# BSK5.net
KiCad netlist of a schematic drawn in EAGLE
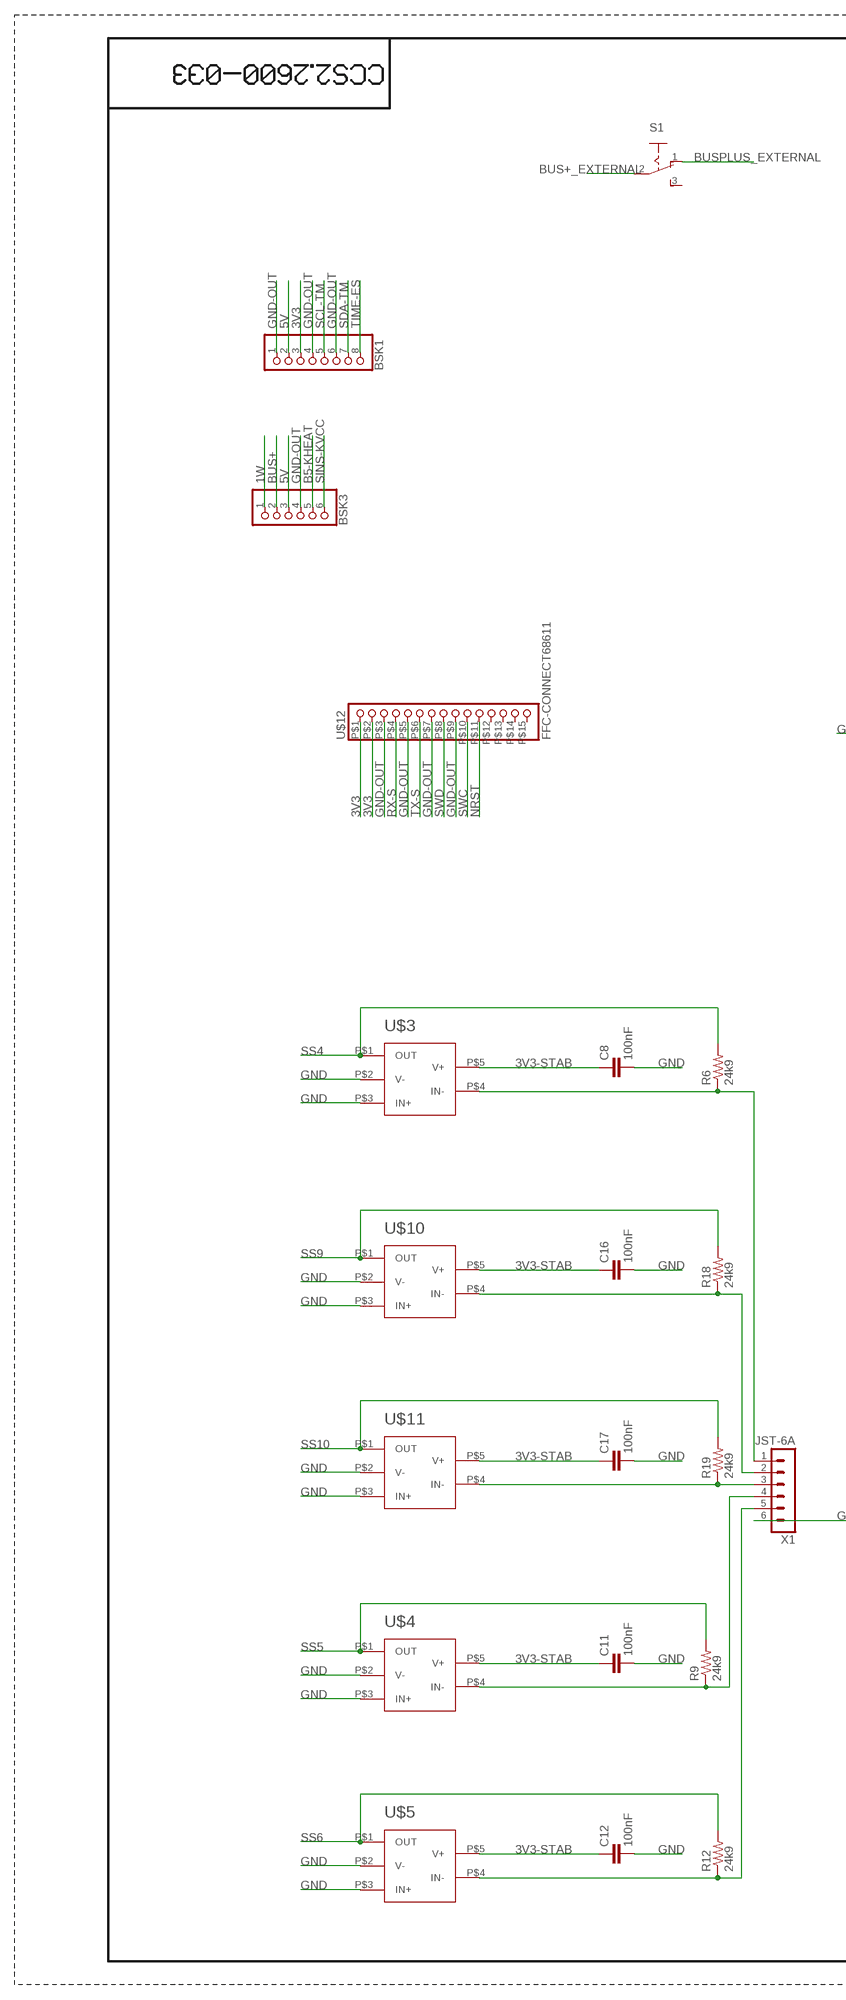
[diagram p0: schematic, sheet 1, part 1 of 3]
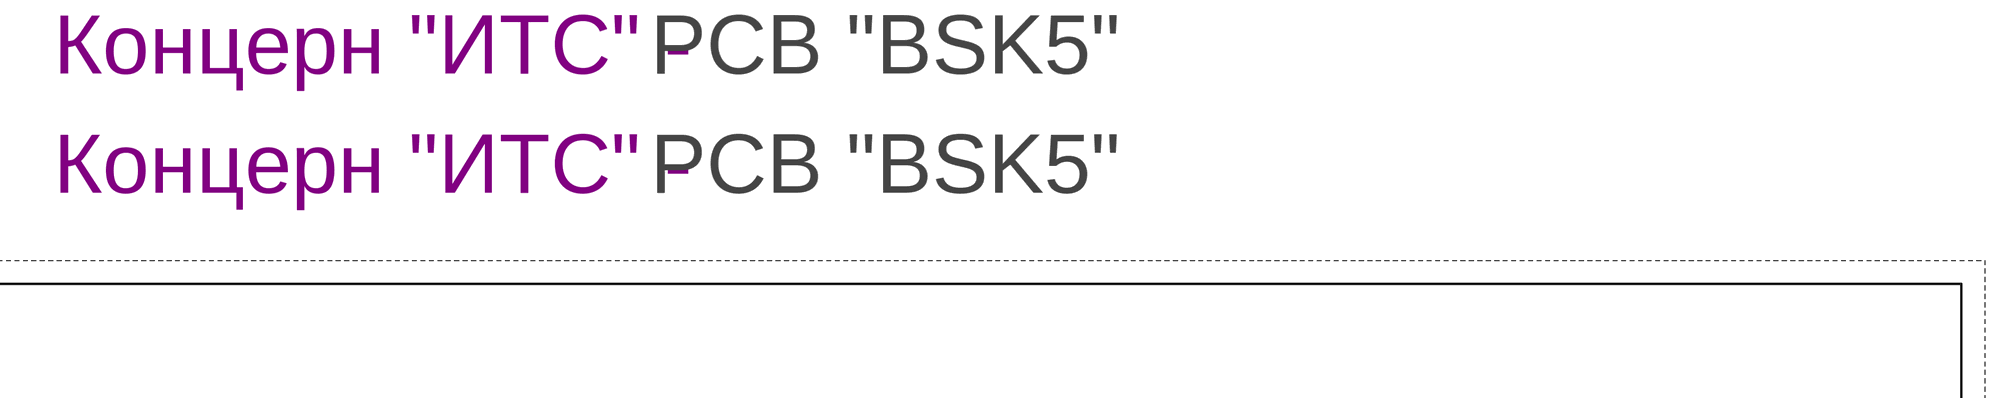
[diagram p1: schematic, sheet 1, part 2 of 3]
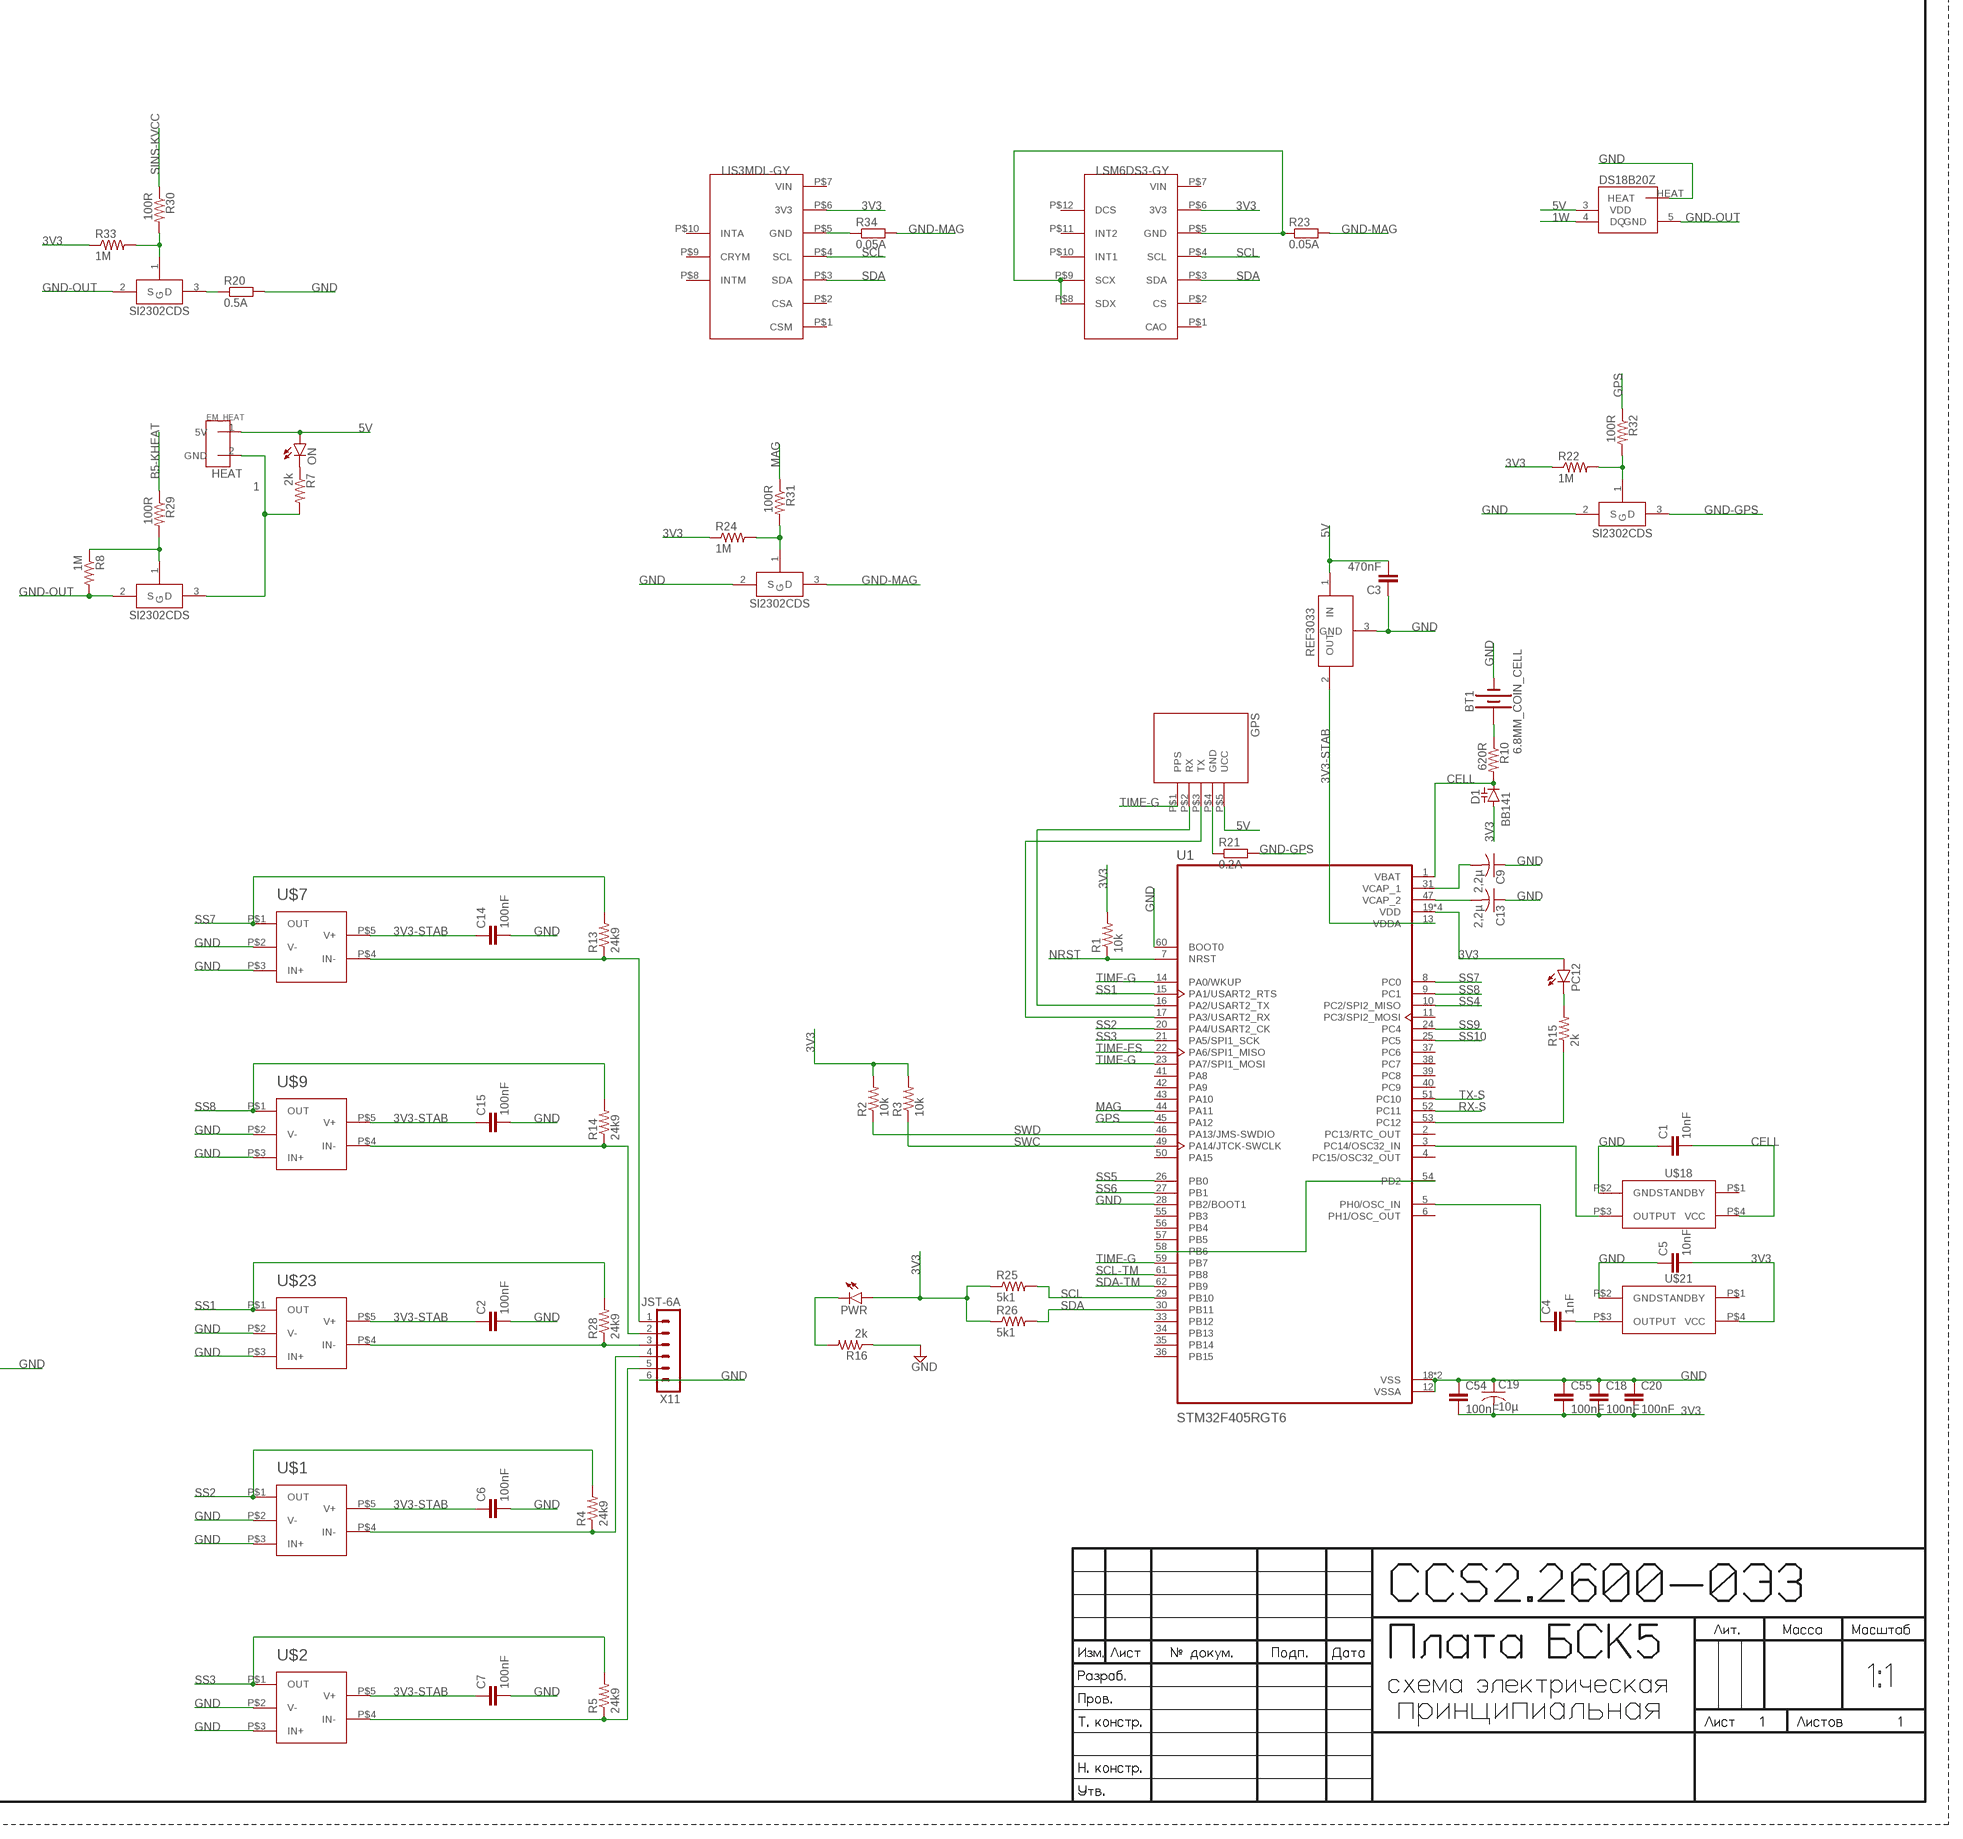
[diagram p2: schematic, sheet 1, part 3 of 3]

(export (version "E")
  (design (tool "Eeschema 10.0.6"))
  (components
    (comp (ref "BSK1")
      (value "PINHD-1X8")
      (footprint "eagle-import:1X08")
      (libsource (lib "eagle-import") (part "PINHD-1X8"))
    )
    (comp (ref "BSK3")
      (value "PINHD-1X6")
      (footprint "eagle-import:1X06")
      (libsource (lib "eagle-import") (part "PINHD-1X6"))
    )
    (comp (ref "BT1")
      (value "6.8MM_COIN_CELL")
      (footprint "eagle-import:BATTCON-6.8MM")
      (libsource (lib "eagle-import") (part "BATTERY-6.8MM_SMD"))
    )
    (comp (ref "C1")
      (value "10nF")
      (footprint "eagle-import:C0603")
      (libsource (lib "eagle-import") (part "C-EUC0603"))
    )
    (comp (ref "C2")
      (value "100nF")
      (footprint "eagle-import:C0603")
      (libsource (lib "eagle-import") (part "C-EUC0603"))
    )
    (comp (ref "C3")
      (value "470nF")
      (footprint "eagle-import:C0603")
      (libsource (lib "eagle-import") (part "C-EUC0603"))
    )
    (comp (ref "C4")
      (value "1nF")
      (footprint "eagle-import:C0603")
      (libsource (lib "eagle-import") (part "C-EUC0603"))
    )
    (comp (ref "C5")
      (value "10nF")
      (footprint "eagle-import:C0603")
      (libsource (lib "eagle-import") (part "C-EUC0603"))
    )
    (comp (ref "C6")
      (value "100nF")
      (footprint "eagle-import:C0603")
      (libsource (lib "eagle-import") (part "C-EUC0603"))
    )
    (comp (ref "C7")
      (value "100nF")
      (footprint "eagle-import:C0603")
      (libsource (lib "eagle-import") (part "C-EUC0603"))
    )
    (comp (ref "C8")
      (value "100nF")
      (footprint "eagle-import:C0603")
      (libsource (lib "eagle-import") (part "C-EUC0603"))
    )
    (comp (ref "C9")
      (value "2,2µ")
      (footprint "eagle-import:C0603")
      (libsource (lib "eagle-import") (part "C-USC0603"))
    )
    (comp (ref "C11")
      (value "100nF")
      (footprint "eagle-import:C0603")
      (libsource (lib "eagle-import") (part "C-EUC0603"))
    )
    (comp (ref "C12")
      (value "100nF")
      (footprint "eagle-import:C0603")
      (libsource (lib "eagle-import") (part "C-EUC0603"))
    )
    (comp (ref "C13")
      (value "2,2µ")
      (footprint "eagle-import:C0603")
      (libsource (lib "eagle-import") (part "C-USC0603"))
    )
    (comp (ref "C14")
      (value "100nF")
      (footprint "eagle-import:C0603")
      (libsource (lib "eagle-import") (part "C-EUC0603"))
    )
    (comp (ref "C15")
      (value "100nF")
      (footprint "eagle-import:C0603")
      (libsource (lib "eagle-import") (part "C-EUC0603"))
    )
    (comp (ref "C16")
      (value "100nF")
      (footprint "eagle-import:C0603")
      (libsource (lib "eagle-import") (part "C-EUC0603"))
    )
    (comp (ref "C17")
      (value "100nF")
      (footprint "eagle-import:C0603")
      (libsource (lib "eagle-import") (part "C-EUC0603"))
    )
    (comp (ref "C18")
      (value "100nF")
      (footprint "eagle-import:C0603")
      (libsource (lib "eagle-import") (part "C-EUC0603"))
    )
    (comp (ref "C19")
      (value "10µ")
      (footprint "eagle-import:C1206")
      (libsource (lib "eagle-import") (part "C-USC1206"))
    )
    (comp (ref "C20")
      (value "100nF")
      (footprint "eagle-import:C0603")
      (libsource (lib "eagle-import") (part "C-EUC0603"))
    )
    (comp (ref "C54")
      (value "100nF")
      (footprint "eagle-import:C0603")
      (libsource (lib "eagle-import") (part "C-EUC0603"))
    )
    (comp (ref "C55")
      (value "100nF")
      (footprint "eagle-import:C0603")
      (libsource (lib "eagle-import") (part "C-EUC0603"))
    )
    (comp (ref "D1")
      (value "BB141")
      (footprint "eagle-import:SOD523")
      (libsource (lib "eagle-import") (part "BB141"))
    )
    (comp (ref "DS18B20Z1")
      (value "DS18B20Z")
      (footprint "eagle-import:SOIC8+HEAT_S")
      (libsource (lib "eagle-import") (part "DS18B20Z"))
    )
    (comp (ref "GPS")
      (value "GPSNEO6M")
      (footprint "eagle-import:GPS-NEO6M")
      (libsource (lib "eagle-import") (part "GPSNEO6M"))
    )
    (comp (ref "HEATER")
      (value "EM_HEAT")
      (footprint "eagle-import:EM_HEAT")
      (libsource (lib "eagle-import") (part "EM_HEAT"))
    )
    (comp (ref "LIS3MDL-GY")
      (value "LIS3MDL-GY")
      (footprint "eagle-import:LIS3MDL-GY")
      (libsource (lib "eagle-import") (part "LIS3MDL-GY"))
    )
    (comp (ref "LSM6DS3-GY")
      (value "LSM6DS3-GY")
      (footprint "eagle-import:LSM6DS3-GY")
      (libsource (lib "eagle-import") (part "LSM6DS3-GY"))
    )
    (comp (ref "ON")
      (value "LEDCHIPLED_0603")
      (footprint "eagle-import:CHIPLED_0603")
      (libsource (lib "eagle-import") (part "LEDCHIPLED_0603"))
    )
    (comp (ref "PC12")
      (value "LEDCHIPLED_0603")
      (footprint "eagle-import:CHIPLED_0603")
      (libsource (lib "eagle-import") (part "LEDCHIPLED_0603"))
    )
    (comp (ref "PWR")
      (value "LEDCHIPLED_0603")
      (footprint "eagle-import:CHIPLED_0603")
      (libsource (lib "eagle-import") (part "LEDCHIPLED_0603"))
    )
    (comp (ref "R1")
      (value "10k")
      (footprint "eagle-import:R0603")
      (libsource (lib "eagle-import") (part "R-US_R0603"))
    )
    (comp (ref "R2")
      (value "10k")
      (footprint "eagle-import:R0603")
      (libsource (lib "eagle-import") (part "R-US_R0603"))
    )
    (comp (ref "R3")
      (value "10k")
      (footprint "eagle-import:R0603")
      (libsource (lib "eagle-import") (part "R-US_R0603"))
    )
    (comp (ref "R4")
      (value "24k9")
      (footprint "eagle-import:R0603")
      (libsource (lib "eagle-import") (part "R-US_R0603"))
    )
    (comp (ref "R5")
      (value "24k9")
      (footprint "eagle-import:R0603")
      (libsource (lib "eagle-import") (part "R-US_R0603"))
    )
    (comp (ref "R6")
      (value "24k9")
      (footprint "eagle-import:R0603")
      (libsource (lib "eagle-import") (part "R-US_R0603"))
    )
    (comp (ref "R7")
      (value "2k")
      (footprint "eagle-import:R0603")
      (libsource (lib "eagle-import") (part "R-US_R0603"))
    )
    (comp (ref "R8")
      (value "1M")
      (footprint "eagle-import:R0603")
      (libsource (lib "eagle-import") (part "R-US_R0603"))
    )
    (comp (ref "R9")
      (value "24k9")
      (footprint "eagle-import:R0603")
      (libsource (lib "eagle-import") (part "R-US_R0603"))
    )
    (comp (ref "R10")
      (value "620R")
      (footprint "eagle-import:R0603")
      (libsource (lib "eagle-import") (part "R-US_R0603"))
    )
    (comp (ref "R12")
      (value "24k9")
      (footprint "eagle-import:R0603")
      (libsource (lib "eagle-import") (part "R-US_R0603"))
    )
    (comp (ref "R13")
      (value "24k9")
      (footprint "eagle-import:R0603")
      (libsource (lib "eagle-import") (part "R-US_R0603"))
    )
    (comp (ref "R14")
      (value "24k9")
      (footprint "eagle-import:R0603")
      (libsource (lib "eagle-import") (part "R-US_R0603"))
    )
    (comp (ref "R15")
      (value "2k")
      (footprint "eagle-import:R0603")
      (libsource (lib "eagle-import") (part "R-US_R0603"))
    )
    (comp (ref "R16")
      (value "2k")
      (footprint "eagle-import:R0603")
      (libsource (lib "eagle-import") (part "R-US_R0603"))
    )
    (comp (ref "R18")
      (value "24k9")
      (footprint "eagle-import:R0603")
      (libsource (lib "eagle-import") (part "R-US_R0603"))
    )
    (comp (ref "R19")
      (value "24k9")
      (footprint "eagle-import:R0603")
      (libsource (lib "eagle-import") (part "R-US_R0603"))
    )
    (comp (ref "R20")
      (value "0.5A")
      (footprint "eagle-import:R1210")
      (libsource (lib "eagle-import") (part "R-EU_R1210"))
    )
    (comp (ref "R21")
      (value "0.2A")
      (footprint "eagle-import:R1210")
      (libsource (lib "eagle-import") (part "R-EU_R1210"))
    )
    (comp (ref "R22")
      (value "1M")
      (footprint "eagle-import:R0603")
      (libsource (lib "eagle-import") (part "R-US_R0603"))
    )
    (comp (ref "R23")
      (value "0.05A")
      (footprint "eagle-import:R1210")
      (libsource (lib "eagle-import") (part "R-EU_R1210"))
    )
    (comp (ref "R24")
      (value "1M")
      (footprint "eagle-import:R0603")
      (libsource (lib "eagle-import") (part "R-US_R0603"))
    )
    (comp (ref "R25")
      (value "5k1")
      (footprint "eagle-import:R0603")
      (libsource (lib "eagle-import") (part "R-US_R0603"))
    )
    (comp (ref "R26")
      (value "5k1")
      (footprint "eagle-import:R0603")
      (libsource (lib "eagle-import") (part "R-US_R0603"))
    )
    (comp (ref "R28")
      (value "24k9")
      (footprint "eagle-import:R0603")
      (libsource (lib "eagle-import") (part "R-US_R0603"))
    )
    (comp (ref "R29")
      (value "100R")
      (footprint "eagle-import:R0603")
      (libsource (lib "eagle-import") (part "R-US_R0603"))
    )
    (comp (ref "R30")
      (value "100R")
      (footprint "eagle-import:R0603")
      (libsource (lib "eagle-import") (part "R-US_R0603"))
    )
    (comp (ref "R31")
      (value "100R")
      (footprint "eagle-import:R0603")
      (libsource (lib "eagle-import") (part "R-US_R0603"))
    )
    (comp (ref "R32")
      (value "100R")
      (footprint "eagle-import:R0603")
      (libsource (lib "eagle-import") (part "R-US_R0603"))
    )
    (comp (ref "R33")
      (value "1M")
      (footprint "eagle-import:R0603")
      (libsource (lib "eagle-import") (part "R-US_R0603"))
    )
    (comp (ref "R34")
      (value "0.05A")
      (footprint "eagle-import:R1210")
      (libsource (lib "eagle-import") (part "R-EU_R1210"))
    )
    (comp (ref "S1")
      (value "UNICS-SWITCH")
      (footprint "eagle-import:UNICS-SWITCH")
      (libsource (lib "eagle-import") (part "UNICS-SWITCH"))
    )
    (comp (ref "U$1")
      (value "LMC7101")
      (footprint "eagle-import:LMC7101")
      (libsource (lib "eagle-import") (part "LMC7101"))
    )
    (comp (ref "U$2")
      (value "LMC7101")
      (footprint "eagle-import:LMC7101")
      (libsource (lib "eagle-import") (part "LMC7101"))
    )
    (comp (ref "U$3")
      (value "LMC7101")
      (footprint "eagle-import:LMC7101")
      (libsource (lib "eagle-import") (part "LMC7101"))
    )
    (comp (ref "U$4")
      (value "LMC7101")
      (footprint "eagle-import:LMC7101")
      (libsource (lib "eagle-import") (part "LMC7101"))
    )
    (comp (ref "U$5")
      (value "LMC7101")
      (footprint "eagle-import:LMC7101")
      (libsource (lib "eagle-import") (part "LMC7101"))
    )
    (comp (ref "U$6")
      (value "REF3033")
      (footprint "eagle-import:SOT23-3")
      (libsource (lib "eagle-import") (part "REF3033"))
    )
    (comp (ref "U$7")
      (value "LMC7101")
      (footprint "eagle-import:LMC7101")
      (libsource (lib "eagle-import") (part "LMC7101"))
    )
    (comp (ref "U$8")
      (value "SI2302CDS")
      (footprint "eagle-import:SOT23-3")
      (libsource (lib "eagle-import") (part "SI2302CDS"))
    )
    (comp (ref "U$9")
      (value "LMC7101")
      (footprint "eagle-import:LMC7101")
      (libsource (lib "eagle-import") (part "LMC7101"))
    )
    (comp (ref "U$10")
      (value "LMC7101")
      (footprint "eagle-import:LMC7101")
      (libsource (lib "eagle-import") (part "LMC7101"))
    )
    (comp (ref "U$11")
      (value "LMC7101")
      (footprint "eagle-import:LMC7101")
      (libsource (lib "eagle-import") (part "LMC7101"))
    )
    (comp (ref "U$12")
      (value "FFC-CONNECT68611")
      (footprint "eagle-import:68611")
      (libsource (lib "eagle-import") (part "FFC-CONNECT68611"))
    )
    (comp (ref "U$13")
      (value "PCB \"BSK5\"")
      (footprint "eagle-import:ITS-LOGO")
      (libsource (lib "eagle-import") (part "ITS-LOGOPCB-{dblquote}{dblquote}"))
    )
    (comp (ref "U$18")
      (value "Q32.768")
      (footprint "eagle-import:Q32.768")
      (libsource (lib "eagle-import") (part "Q32.768"))
    )
    (comp (ref "U$19")
      (value "SI2302CDS")
      (footprint "eagle-import:SOT23-3")
      (libsource (lib "eagle-import") (part "SI2302CDS"))
    )
    (comp (ref "U$20")
      (value "SI2302CDS")
      (footprint "eagle-import:SOT23-3")
      (libsource (lib "eagle-import") (part "SI2302CDS"))
    )
    (comp (ref "U$21")
      (value "Q24")
      (footprint "eagle-import:Q24")
      (libsource (lib "eagle-import") (part "Q24"))
    )
    (comp (ref "U$22")
      (value "SI2302CDS")
      (footprint "eagle-import:SOT23-3")
      (libsource (lib "eagle-import") (part "SI2302CDS"))
    )
    (comp (ref "U$23")
      (value "LMC7101")
      (footprint "eagle-import:LMC7101")
      (libsource (lib "eagle-import") (part "LMC7101"))
    )
    (comp (ref "U$26")
      (value "PCB \"BSK5\"")
      (footprint "eagle-import:ITS-LOGO")
      (libsource (lib "eagle-import") (part "ITS-LOGOPCB-{dblquote}{dblquote}"))
    )
    (comp (ref "U1")
      (value "STM32F405RGT6")
      (footprint "eagle-import:QFP50P1200X1200X160-64N")
      (fields (field (name "DIGI-KEY_PART_NUMBER") "497-11767-ND") (field (name "MF") "STMicroelectronics"))
      (libsource (lib "eagle-import") (part "STM32F405RGT6"))
    )
    (comp (ref "X1")
      (value "JST-6A")
      (footprint "eagle-import:B6B-EH-A")
      (libsource (lib "eagle-import") (part "JST-6A"))
    )
    (comp (ref "X11")
      (value "JST-6A")
      (footprint "eagle-import:B6B-EH-A")
      (libsource (lib "eagle-import") (part "JST-6A"))
    )
  )
  (nets
    (net (code "1") (name "/1") (class "Default")
      (node (ref "HEATER") (pin "2") (pinfunction "GND_2") (pintype "bidirectional"))
      (node (ref "R7") (pin "2") (pinfunction "2_2") (pintype "passive"))
      (node (ref "U$8") (pin "3") (pinfunction "D_3") (pintype "bidirectional"))
    )
    (net (code "2") (name "/1W") (class "Default")
      (node (ref "BSK3") (pin "1") (pinfunction "1_1") (pintype "passive"))
      (node (ref "DS18B20Z1") (pin "4") (pinfunction "DQ_4") (pintype "bidirectional"))
    )
    (net (code "3") (name "/3V3") (class "Default")
      (node (ref "BSK1") (pin "3") (pinfunction "3_3") (pintype "passive"))
      (node (ref "C18") (pin "2") (pinfunction "2_2") (pintype "passive"))
      (node (ref "C19") (pin "2") (pinfunction "2_2") (pintype "passive"))
      (node (ref "C20") (pin "2") (pinfunction "2_2") (pintype "passive"))
      (node (ref "C5") (pin "2") (pinfunction "2_2") (pintype "passive"))
      (node (ref "C54") (pin "2") (pinfunction "2_2") (pintype "passive"))
      (node (ref "C55") (pin "2") (pinfunction "2_2") (pintype "passive"))
      (node (ref "D1") (pin "A") (pinfunction "A_A") (pintype "passive"))
      (node (ref "LIS3MDL-GY") (pin "P$6") (pinfunction "3V3_P$6") (pintype "bidirectional"))
      (node (ref "LSM6DS3-GY") (pin "P$6") (pinfunction "3V3_P$6") (pintype "bidirectional"))
      (node (ref "PC12") (pin "A") (pinfunction "A_A") (pintype "passive"))
      (node (ref "PWR") (pin "A") (pinfunction "A_A") (pintype "passive"))
      (node (ref "R1") (pin "2") (pinfunction "2_2") (pintype "passive"))
      (node (ref "R2") (pin "2") (pinfunction "2_2") (pintype "passive"))
      (node (ref "R22") (pin "1") (pinfunction "1_1") (pintype "passive"))
      (node (ref "R24") (pin "1") (pinfunction "1_1") (pintype "passive"))
      (node (ref "R25") (pin "1") (pinfunction "1_1") (pintype "passive"))
      (node (ref "R26") (pin "1") (pinfunction "1_1") (pintype "passive"))
      (node (ref "R3") (pin "2") (pinfunction "2_2") (pintype "passive"))
      (node (ref "R33") (pin "1") (pinfunction "1_1") (pintype "passive"))
      (node (ref "U$12") (pin "P$1") (pinfunction "1_P$1") (pintype "passive"))
      (node (ref "U$12") (pin "P$2") (pinfunction "2_P$2") (pintype "passive"))
      (node (ref "U$21") (pin "P$4") (pinfunction "VCC_P$4") (pintype "bidirectional"))
      (node (ref "U1") (pin "19") (pinfunction "VDD_19") (pintype "power_in"))
      (node (ref "U1") (pin "32") (pinfunction "VDD_32") (pintype "power_in"))
      (node (ref "U1") (pin "48") (pinfunction "VDD_48") (pintype "power_in"))
      (node (ref "U1") (pin "64") (pinfunction "VDD_64") (pintype "power_in"))
    )
    (net (code "4") (name "/3V3-STAB") (class "Default")
      (node (ref "C11") (pin "1") (pinfunction "1_1") (pintype "passive"))
      (node (ref "C12") (pin "1") (pinfunction "1_1") (pintype "passive"))
      (node (ref "C14") (pin "1") (pinfunction "1_1") (pintype "passive"))
      (node (ref "C15") (pin "1") (pinfunction "1_1") (pintype "passive"))
      (node (ref "C16") (pin "1") (pinfunction "1_1") (pintype "passive"))
      (node (ref "C17") (pin "1") (pinfunction "1_1") (pintype "passive"))
      (node (ref "C2") (pin "1") (pinfunction "1_1") (pintype "passive"))
      (node (ref "C6") (pin "1") (pinfunction "1_1") (pintype "passive"))
      (node (ref "C7") (pin "1") (pinfunction "1_1") (pintype "passive"))
      (node (ref "C8") (pin "1") (pinfunction "1_1") (pintype "passive"))
      (node (ref "U$1") (pin "P$5") (pinfunction "V+_P$5") (pintype "bidirectional"))
      (node (ref "U$10") (pin "P$5") (pinfunction "V+_P$5") (pintype "bidirectional"))
      (node (ref "U$11") (pin "P$5") (pinfunction "V+_P$5") (pintype "bidirectional"))
      (node (ref "U$2") (pin "P$5") (pinfunction "V+_P$5") (pintype "bidirectional"))
      (node (ref "U$23") (pin "P$5") (pinfunction "V+_P$5") (pintype "bidirectional"))
      (node (ref "U$3") (pin "P$5") (pinfunction "V+_P$5") (pintype "bidirectional"))
      (node (ref "U$4") (pin "P$5") (pinfunction "V+_P$5") (pintype "bidirectional"))
      (node (ref "U$5") (pin "P$5") (pinfunction "V+_P$5") (pintype "bidirectional"))
      (node (ref "U$6") (pin "2") (pinfunction "OUT_2") (pintype "output"))
      (node (ref "U$7") (pin "P$5") (pinfunction "V+_P$5") (pintype "bidirectional"))
      (node (ref "U$9") (pin "P$5") (pinfunction "V+_P$5") (pintype "bidirectional"))
      (node (ref "U1") (pin "13") (pinfunction "VDDA_13") (pintype "power_in"))
    )
    (net (code "5") (name "/5V") (class "Default")
      (node (ref "BSK1") (pin "2") (pinfunction "2_2") (pintype "passive"))
      (node (ref "BSK3") (pin "3") (pinfunction "3_3") (pintype "passive"))
      (node (ref "C3") (pin "2") (pinfunction "2_2") (pintype "passive"))
      (node (ref "DS18B20Z1") (pin "3") (pinfunction "VDD_3") (pintype "bidirectional"))
      (node (ref "GPS") (pin "P$5") (pinfunction "UCC_P$5") (pintype "bidirectional"))
      (node (ref "HEATER") (pin "1") (pinfunction "5V_1") (pintype "bidirectional"))
      (node (ref "ON") (pin "A") (pinfunction "A_A") (pintype "passive"))
      (node (ref "U$6") (pin "1") (pinfunction "IN_1") (pintype "input"))
    )
    (net (code "6") (name "/B5-KHEAT") (class "Default")
      (node (ref "BSK3") (pin "5") (pinfunction "5_5") (pintype "passive"))
      (node (ref "R29") (pin "1") (pinfunction "1_1") (pintype "passive"))
    )
    (net (code "7") (name "/BUS+") (class "Default")
      (node (ref "BSK3") (pin "2") (pinfunction "2_2") (pintype "passive"))
    )
    (net (code "8") (name "/BUS+_EXTERNAL") (class "Default")
      (node (ref "S1") (pin "2") (pinfunction "P_2") (pintype "passive"))
    )
    (net (code "9") (name "/BUSPLUS_EXTERNAL") (class "Default")
      (node (ref "S1") (pin "1") (pinfunction "O_1") (pintype "passive"))
    )
    (net (code "10") (name "/CELL") (class "Default")
      (node (ref "C1") (pin "2") (pinfunction "2_2") (pintype "passive"))
      (node (ref "D1") (pin "C") (pinfunction "C_C") (pintype "passive"))
      (node (ref "R10") (pin "2") (pinfunction "2_2") (pintype "passive"))
      (node (ref "U$18") (pin "P$4") (pinfunction "VCC_P$4") (pintype "bidirectional"))
      (node (ref "U1") (pin "1") (pinfunction "VBAT_1") (pintype "power_in"))
    )
    (net (code "11") (name "/GND-GPS") (class "Default")
      (node (ref "R21") (pin "2") (pinfunction "2_2") (pintype "passive"))
      (node (ref "U$20") (pin "3") (pinfunction "D_3") (pintype "bidirectional"))
    )
    (net (code "12") (name "/GND-MAG") (class "Default")
      (node (ref "R23") (pin "2") (pinfunction "2_2") (pintype "passive"))
      (node (ref "R34") (pin "2") (pinfunction "2_2") (pintype "passive"))
      (node (ref "U$19") (pin "3") (pinfunction "D_3") (pintype "bidirectional"))
    )
    (net (code "13") (name "/GND-OUT") (class "Default")
      (node (ref "BSK1") (pin "1") (pinfunction "1_1") (pintype "passive"))
      (node (ref "BSK1") (pin "4") (pinfunction "4_4") (pintype "passive"))
      (node (ref "BSK1") (pin "6") (pinfunction "6_6") (pintype "passive"))
      (node (ref "BSK3") (pin "4") (pinfunction "4_4") (pintype "passive"))
      (node (ref "DS18B20Z1") (pin "5") (pinfunction "GND_5") (pintype "bidirectional"))
      (node (ref "R8") (pin "2") (pinfunction "2_2") (pintype "passive"))
      (node (ref "U$12") (pin "P$3") (pinfunction "3_P$3") (pintype "passive"))
      (node (ref "U$12") (pin "P$5") (pinfunction "5_P$5") (pintype "passive"))
      (node (ref "U$12") (pin "P$7") (pinfunction "7_P$7") (pintype "passive"))
      (node (ref "U$12") (pin "P$9") (pinfunction "9_P$9") (pintype "passive"))
      (node (ref "U$22") (pin "2") (pinfunction "S_2") (pintype "bidirectional"))
      (node (ref "U$8") (pin "2") (pinfunction "S_2") (pintype "bidirectional"))
    )
    (net (code "14") (name "/GPS") (class "Default")
      (node (ref "R32") (pin "1") (pinfunction "1_1") (pintype "passive"))
      (node (ref "U1") (pin "45") (pinfunction "PA12_45") (pintype "bidirectional"))
    )
    (net (code "15") (name "/MAG") (class "Default")
      (node (ref "R31") (pin "1") (pinfunction "1_1") (pintype "passive"))
      (node (ref "U1") (pin "44") (pinfunction "PA11_44") (pintype "bidirectional"))
    )
    (net (code "16") (name "/NRST") (class "Default")
      (node (ref "R1") (pin "1") (pinfunction "1_1") (pintype "passive"))
      (node (ref "U$12") (pin "P$11") (pinfunction "11_P$11") (pintype "passive"))
      (node (ref "U1") (pin "7") (pinfunction "NRST_7") (pintype "bidirectional"))
    )
    (net (code "17") (name "/RX-S") (class "Default")
      (node (ref "U$12") (pin "P$4") (pinfunction "4_P$4") (pintype "passive"))
      (node (ref "U1") (pin "52") (pinfunction "PC11_52") (pintype "bidirectional"))
    )
    (net (code "18") (name "/SCL") (class "Default")
      (node (ref "LIS3MDL-GY") (pin "P$4") (pinfunction "SCL_P$4") (pintype "bidirectional"))
      (node (ref "LSM6DS3-GY") (pin "P$4") (pinfunction "SCL_P$4") (pintype "bidirectional"))
      (node (ref "R25") (pin "2") (pinfunction "2_2") (pintype "passive"))
      (node (ref "U1") (pin "29") (pinfunction "PB10_29") (pintype "bidirectional"))
    )
    (net (code "19") (name "/SCL-TM") (class "Default")
      (node (ref "BSK1") (pin "5") (pinfunction "5_5") (pintype "passive"))
      (node (ref "U1") (pin "61") (pinfunction "PB8_61") (pintype "bidirectional"))
    )
    (net (code "20") (name "/SDA") (class "Default")
      (node (ref "LIS3MDL-GY") (pin "P$3") (pinfunction "SDA_P$3") (pintype "bidirectional"))
      (node (ref "LSM6DS3-GY") (pin "P$3") (pinfunction "SDA_P$3") (pintype "bidirectional"))
      (node (ref "R26") (pin "2") (pinfunction "2_2") (pintype "passive"))
      (node (ref "U1") (pin "30") (pinfunction "PB11_30") (pintype "bidirectional"))
    )
    (net (code "21") (name "/SDA-TM") (class "Default")
      (node (ref "BSK1") (pin "7") (pinfunction "7_7") (pintype "passive"))
      (node (ref "U1") (pin "62") (pinfunction "PB9_62") (pintype "bidirectional"))
    )
    (net (code "22") (name "/SINS-KVCC") (class "Default")
      (node (ref "BSK3") (pin "6") (pinfunction "6_6") (pintype "passive"))
      (node (ref "R30") (pin "1") (pinfunction "1_1") (pintype "passive"))
    )
    (net (code "23") (name "/SS1") (class "Default")
      (node (ref "R28") (pin "2") (pinfunction "2_2") (pintype "passive"))
      (node (ref "U$23") (pin "P$1") (pinfunction "OUT_P$1") (pintype "bidirectional"))
      (node (ref "U1") (pin "15") (pinfunction "PA1/USART2_RTS_15") (pintype "bidirectional"))
    )
    (net (code "24") (name "/SS2") (class "Default")
      (node (ref "R4") (pin "2") (pinfunction "2_2") (pintype "passive"))
      (node (ref "U$1") (pin "P$1") (pinfunction "OUT_P$1") (pintype "bidirectional"))
      (node (ref "U1") (pin "20") (pinfunction "PA4/USART2_CK_20") (pintype "bidirectional"))
    )
    (net (code "25") (name "/SS3") (class "Default")
      (node (ref "R5") (pin "2") (pinfunction "2_2") (pintype "passive"))
      (node (ref "U$2") (pin "P$1") (pinfunction "OUT_P$1") (pintype "bidirectional"))
      (node (ref "U1") (pin "21") (pinfunction "PA5/SPI1_SCK_21") (pintype "bidirectional"))
    )
    (net (code "26") (name "/SS4") (class "Default")
      (node (ref "R6") (pin "2") (pinfunction "2_2") (pintype "passive"))
      (node (ref "U$3") (pin "P$1") (pinfunction "OUT_P$1") (pintype "bidirectional"))
      (node (ref "U1") (pin "10") (pinfunction "PC2/SPI2_MISO_10") (pintype "bidirectional"))
    )
    (net (code "27") (name "/SS5") (class "Default")
      (node (ref "R9") (pin "2") (pinfunction "2_2") (pintype "passive"))
      (node (ref "U$4") (pin "P$1") (pinfunction "OUT_P$1") (pintype "bidirectional"))
      (node (ref "U1") (pin "26") (pinfunction "PB0_26") (pintype "bidirectional"))
    )
    (net (code "28") (name "/SS6") (class "Default")
      (node (ref "R12") (pin "2") (pinfunction "2_2") (pintype "passive"))
      (node (ref "U$5") (pin "P$1") (pinfunction "OUT_P$1") (pintype "bidirectional"))
      (node (ref "U1") (pin "27") (pinfunction "PB1_27") (pintype "bidirectional"))
    )
    (net (code "29") (name "/SS7") (class "Default")
      (node (ref "R13") (pin "2") (pinfunction "2_2") (pintype "passive"))
      (node (ref "U$7") (pin "P$1") (pinfunction "OUT_P$1") (pintype "bidirectional"))
      (node (ref "U1") (pin "8") (pinfunction "PC0_8") (pintype "bidirectional"))
    )
    (net (code "30") (name "/SS8") (class "Default")
      (node (ref "R14") (pin "2") (pinfunction "2_2") (pintype "passive"))
      (node (ref "U$9") (pin "P$1") (pinfunction "OUT_P$1") (pintype "bidirectional"))
      (node (ref "U1") (pin "9") (pinfunction "PC1_9") (pintype "bidirectional"))
    )
    (net (code "31") (name "/SS9") (class "Default")
      (node (ref "R18") (pin "2") (pinfunction "2_2") (pintype "passive"))
      (node (ref "U$10") (pin "P$1") (pinfunction "OUT_P$1") (pintype "bidirectional"))
      (node (ref "U1") (pin "24") (pinfunction "PC4_24") (pintype "bidirectional"))
    )
    (net (code "32") (name "/SS10") (class "Default")
      (node (ref "R19") (pin "2") (pinfunction "2_2") (pintype "passive"))
      (node (ref "U$11") (pin "P$1") (pinfunction "OUT_P$1") (pintype "bidirectional"))
      (node (ref "U1") (pin "25") (pinfunction "PC5_25") (pintype "bidirectional"))
    )
    (net (code "33") (name "/SWC") (class "Default")
      (node (ref "R3") (pin "1") (pinfunction "1_1") (pintype "passive"))
      (node (ref "U$12") (pin "P$10") (pinfunction "10_P$10") (pintype "passive"))
      (node (ref "U1") (pin "49") (pinfunction "PA14/JTCK-SWCLK_49") (pintype "bidirectional"))
    )
    (net (code "34") (name "/SWD") (class "Default")
      (node (ref "R2") (pin "1") (pinfunction "1_1") (pintype "passive"))
      (node (ref "U$12") (pin "P$8") (pinfunction "8_P$8") (pintype "passive"))
      (node (ref "U1") (pin "46") (pinfunction "PA13/JMS-SWDIO_46") (pintype "bidirectional"))
    )
    (net (code "35") (name "/TIME-ES") (class "Default")
      (node (ref "BSK1") (pin "8") (pinfunction "8_8") (pintype "passive"))
      (node (ref "U1") (pin "22") (pinfunction "PA6/SPI1_MISO_22") (pintype "bidirectional"))
    )
    (net (code "36") (name "/TIME-G") (class "Default")
      (node (ref "GPS") (pin "P$1") (pinfunction "PPS_P$1") (pintype "bidirectional"))
      (node (ref "U1") (pin "14") (pinfunction "PA0/WKUP_14") (pintype "bidirectional"))
      (node (ref "U1") (pin "23") (pinfunction "PA7/SPI1_MOSI_23") (pintype "bidirectional"))
      (node (ref "U1") (pin "59") (pinfunction "PB7_59") (pintype "bidirectional"))
    )
    (net (code "37") (name "/TX-S") (class "Default")
      (node (ref "U$12") (pin "P$6") (pinfunction "6_P$6") (pintype "passive"))
      (node (ref "U1") (pin "51") (pinfunction "PC10_51") (pintype "bidirectional"))
    )
    (net (code "38") (name "GND") (class "Default")
      (node (ref "BT1") (pin "-") (pinfunction "-_-") (pintype "power_in"))
      (node (ref "C1") (pin "1") (pinfunction "1_1") (pintype "passive"))
      (node (ref "C11") (pin "2") (pinfunction "2_2") (pintype "passive"))
      (node (ref "C12") (pin "2") (pinfunction "2_2") (pintype "passive"))
      (node (ref "C13") (pin "1") (pinfunction "1_1") (pintype "passive"))
      (node (ref "C14") (pin "2") (pinfunction "2_2") (pintype "passive"))
      (node (ref "C15") (pin "2") (pinfunction "2_2") (pintype "passive"))
      (node (ref "C16") (pin "2") (pinfunction "2_2") (pintype "passive"))
      (node (ref "C17") (pin "2") (pinfunction "2_2") (pintype "passive"))
      (node (ref "C18") (pin "1") (pinfunction "1_1") (pintype "passive"))
      (node (ref "C19") (pin "1") (pinfunction "1_1") (pintype "passive"))
      (node (ref "C2") (pin "2") (pinfunction "2_2") (pintype "passive"))
      (node (ref "C20") (pin "1") (pinfunction "1_1") (pintype "passive"))
      (node (ref "C3") (pin "1") (pinfunction "1_1") (pintype "passive"))
      (node (ref "C5") (pin "1") (pinfunction "1_1") (pintype "passive"))
      (node (ref "C54") (pin "1") (pinfunction "1_1") (pintype "passive"))
      (node (ref "C55") (pin "1") (pinfunction "1_1") (pintype "passive"))
      (node (ref "C6") (pin "2") (pinfunction "2_2") (pintype "passive"))
      (node (ref "C7") (pin "2") (pinfunction "2_2") (pintype "passive"))
      (node (ref "C8") (pin "2") (pinfunction "2_2") (pintype "passive"))
      (node (ref "C9") (pin "1") (pinfunction "1_1") (pintype "passive"))
      (node (ref "DS18B20Z1") (pin "HEAT") (pinfunction "HEAT_HEAT") (pintype "bidirectional"))
      (node (ref "R16") (pin "1") (pinfunction "1_1") (pintype "passive"))
      (node (ref "R20") (pin "2") (pinfunction "2_2") (pintype "passive"))
      (node (ref "U$1") (pin "P$2") (pinfunction "V-_P$2") (pintype "bidirectional"))
      (node (ref "U$1") (pin "P$3") (pinfunction "IN+_P$3") (pintype "bidirectional"))
      (node (ref "U$10") (pin "P$2") (pinfunction "V-_P$2") (pintype "bidirectional"))
      (node (ref "U$10") (pin "P$3") (pinfunction "IN+_P$3") (pintype "bidirectional"))
      (node (ref "U$11") (pin "P$2") (pinfunction "V-_P$2") (pintype "bidirectional"))
      (node (ref "U$11") (pin "P$3") (pinfunction "IN+_P$3") (pintype "bidirectional"))
      (node (ref "U$18") (pin "P$2") (pinfunction "GND_P$2") (pintype "bidirectional"))
      (node (ref "U$19") (pin "2") (pinfunction "S_2") (pintype "bidirectional"))
      (node (ref "U$2") (pin "P$2") (pinfunction "V-_P$2") (pintype "bidirectional"))
      (node (ref "U$2") (pin "P$3") (pinfunction "IN+_P$3") (pintype "bidirectional"))
      (node (ref "U$20") (pin "2") (pinfunction "S_2") (pintype "bidirectional"))
      (node (ref "U$21") (pin "P$2") (pinfunction "GND_P$2") (pintype "bidirectional"))
      (node (ref "U$23") (pin "P$2") (pinfunction "V-_P$2") (pintype "bidirectional"))
      (node (ref "U$23") (pin "P$3") (pinfunction "IN+_P$3") (pintype "bidirectional"))
      (node (ref "U$3") (pin "P$2") (pinfunction "V-_P$2") (pintype "bidirectional"))
      (node (ref "U$3") (pin "P$3") (pinfunction "IN+_P$3") (pintype "bidirectional"))
      (node (ref "U$4") (pin "P$2") (pinfunction "V-_P$2") (pintype "bidirectional"))
      (node (ref "U$4") (pin "P$3") (pinfunction "IN+_P$3") (pintype "bidirectional"))
      (node (ref "U$5") (pin "P$2") (pinfunction "V-_P$2") (pintype "bidirectional"))
      (node (ref "U$5") (pin "P$3") (pinfunction "IN+_P$3") (pintype "bidirectional"))
      (node (ref "U$6") (pin "3") (pinfunction "GND_3") (pintype "power_in"))
      (node (ref "U$7") (pin "P$2") (pinfunction "V-_P$2") (pintype "bidirectional"))
      (node (ref "U$7") (pin "P$3") (pinfunction "IN+_P$3") (pintype "bidirectional"))
      (node (ref "U$9") (pin "P$2") (pinfunction "V-_P$2") (pintype "bidirectional"))
      (node (ref "U$9") (pin "P$3") (pinfunction "IN+_P$3") (pintype "bidirectional"))
      (node (ref "U1") (pin "12") (pinfunction "VSSA_12") (pintype "power_in"))
      (node (ref "U1") (pin "18") (pinfunction "VSS_18") (pintype "power_in"))
      (node (ref "U1") (pin "28") (pinfunction "PB2/BOOT1_28") (pintype "bidirectional"))
      (node (ref "U1") (pin "60") (pinfunction "BOOT0_60") (pintype "bidirectional"))
      (node (ref "U1") (pin "63") (pinfunction "VSS_63") (pintype "power_in"))
      (node (ref "X1") (pin "6") (pinfunction "6_6") (pintype "passive"))
      (node (ref "X11") (pin "6") (pinfunction "6_6") (pintype "passive"))
    )
    (net (code "39") (name "Net-(BT1-Pad+)") (class "Default")
      (node (ref "BT1") (pin "+") (pinfunction "+_+") (pintype "power_in"))
      (node (ref "R10") (pin "1") (pinfunction "1_1") (pintype "passive"))
    )
    (net (code "40") (name "Net-(GPS-GND)") (class "Default")
      (node (ref "GPS") (pin "P$4") (pinfunction "GND_P$4") (pintype "bidirectional"))
      (node (ref "R21") (pin "1") (pinfunction "1_1") (pintype "passive"))
    )
    (net (code "41") (name "Net-(GPS-RX)") (class "Default")
      (node (ref "GPS") (pin "P$2") (pinfunction "RX_P$2") (pintype "bidirectional"))
      (node (ref "U1") (pin "16") (pinfunction "PA2/USART2_TX_16") (pintype "bidirectional"))
    )
    (net (code "42") (name "Net-(GPS-TX)") (class "Default")
      (node (ref "GPS") (pin "P$3") (pinfunction "TX_P$3") (pintype "bidirectional"))
      (node (ref "U1") (pin "17") (pinfunction "PA3/USART2_RX_17") (pintype "bidirectional"))
    )
    (net (code "43") (name "Net-(LIS3MDL-GY-GND)") (class "Default")
      (node (ref "LIS3MDL-GY") (pin "P$5") (pinfunction "GND_P$5") (pintype "bidirectional"))
      (node (ref "R34") (pin "1") (pinfunction "1_1") (pintype "passive"))
    )
    (net (code "44") (name "Net-(LSM6DS3-GY-GND)") (class "Default")
      (node (ref "LSM6DS3-GY") (pin "P$5") (pinfunction "GND_P$5") (pintype "bidirectional"))
      (node (ref "LSM6DS3-GY") (pin "P$8") (pinfunction "SDX_P$8") (pintype "bidirectional"))
      (node (ref "LSM6DS3-GY") (pin "P$9") (pinfunction "SCX_P$9") (pintype "bidirectional"))
      (node (ref "R23") (pin "1") (pinfunction "1_1") (pintype "passive"))
    )
    (net (code "45") (name "Net-(ON-PadC)") (class "Default")
      (node (ref "ON") (pin "C") (pinfunction "C_C") (pintype "passive"))
      (node (ref "R7") (pin "1") (pinfunction "1_1") (pintype "passive"))
    )
    (net (code "46") (name "Net-(PC12-PadC)") (class "Default")
      (node (ref "PC12") (pin "C") (pinfunction "C_C") (pintype "passive"))
      (node (ref "R15") (pin "2") (pinfunction "2_2") (pintype "passive"))
    )
    (net (code "47") (name "Net-(PWR-PadC)") (class "Default")
      (node (ref "PWR") (pin "C") (pinfunction "C_C") (pintype "passive"))
      (node (ref "R16") (pin "2") (pinfunction "2_2") (pintype "passive"))
    )
    (net (code "48") (name "Net-(U$1-IN-)") (class "Default")
      (node (ref "R4") (pin "1") (pinfunction "1_1") (pintype "passive"))
      (node (ref "U$1") (pin "P$4") (pinfunction "IN-_P$4") (pintype "bidirectional"))
      (node (ref "X11") (pin "4") (pinfunction "4_4") (pintype "passive"))
    )
    (net (code "49") (name "Net-(U$2-IN-)") (class "Default")
      (node (ref "R5") (pin "1") (pinfunction "1_1") (pintype "passive"))
      (node (ref "U$2") (pin "P$4") (pinfunction "IN-_P$4") (pintype "bidirectional"))
      (node (ref "X11") (pin "5") (pinfunction "5_5") (pintype "passive"))
    )
    (net (code "50") (name "Net-(U$3-IN-)") (class "Default")
      (node (ref "R6") (pin "1") (pinfunction "1_1") (pintype "passive"))
      (node (ref "U$3") (pin "P$4") (pinfunction "IN-_P$4") (pintype "bidirectional"))
      (node (ref "X1") (pin "1") (pinfunction "1_1") (pintype "passive"))
    )
    (net (code "51") (name "Net-(U$4-IN-)") (class "Default")
      (node (ref "R9") (pin "1") (pinfunction "1_1") (pintype "passive"))
      (node (ref "U$4") (pin "P$4") (pinfunction "IN-_P$4") (pintype "bidirectional"))
      (node (ref "X1") (pin "4") (pinfunction "4_4") (pintype "passive"))
    )
    (net (code "52") (name "Net-(U$5-IN-)") (class "Default")
      (node (ref "R12") (pin "1") (pinfunction "1_1") (pintype "passive"))
      (node (ref "U$5") (pin "P$4") (pinfunction "IN-_P$4") (pintype "bidirectional"))
      (node (ref "X1") (pin "5") (pinfunction "5_5") (pintype "passive"))
    )
    (net (code "53") (name "Net-(U$7-IN-)") (class "Default")
      (node (ref "R13") (pin "1") (pinfunction "1_1") (pintype "passive"))
      (node (ref "U$7") (pin "P$4") (pinfunction "IN-_P$4") (pintype "bidirectional"))
      (node (ref "X11") (pin "1") (pinfunction "1_1") (pintype "passive"))
    )
    (net (code "54") (name "Net-(U$8-G)") (class "Default")
      (node (ref "R29") (pin "2") (pinfunction "2_2") (pintype "passive"))
      (node (ref "R8") (pin "1") (pinfunction "1_1") (pintype "passive"))
      (node (ref "U$8") (pin "1") (pinfunction "G_1") (pintype "bidirectional"))
    )
    (net (code "55") (name "Net-(U$9-IN-)") (class "Default")
      (node (ref "R14") (pin "1") (pinfunction "1_1") (pintype "passive"))
      (node (ref "U$9") (pin "P$4") (pinfunction "IN-_P$4") (pintype "bidirectional"))
      (node (ref "X11") (pin "2") (pinfunction "2_2") (pintype "passive"))
    )
    (net (code "56") (name "Net-(U$10-IN-)") (class "Default")
      (node (ref "R18") (pin "1") (pinfunction "1_1") (pintype "passive"))
      (node (ref "U$10") (pin "P$4") (pinfunction "IN-_P$4") (pintype "bidirectional"))
      (node (ref "X1") (pin "2") (pinfunction "2_2") (pintype "passive"))
    )
    (net (code "57") (name "Net-(U$11-IN-)") (class "Default")
      (node (ref "R19") (pin "1") (pinfunction "1_1") (pintype "passive"))
      (node (ref "U$11") (pin "P$4") (pinfunction "IN-_P$4") (pintype "bidirectional"))
      (node (ref "X1") (pin "3") (pinfunction "3_3") (pintype "passive"))
    )
    (net (code "58") (name "Net-(U$18-OUTPUT)") (class "Default")
      (node (ref "U$18") (pin "P$3") (pinfunction "OUTPUT_P$3") (pintype "bidirectional"))
      (node (ref "U1") (pin "3") (pinfunction "PC14/OSC32_IN_3") (pintype "bidirectional"))
    )
    (net (code "59") (name "Net-(U$19-G)") (class "Default")
      (node (ref "R24") (pin "2") (pinfunction "2_2") (pintype "passive"))
      (node (ref "R31") (pin "2") (pinfunction "2_2") (pintype "passive"))
      (node (ref "U$19") (pin "1") (pinfunction "G_1") (pintype "bidirectional"))
    )
    (net (code "60") (name "Net-(U$20-G)") (class "Default")
      (node (ref "R22") (pin "2") (pinfunction "2_2") (pintype "passive"))
      (node (ref "R32") (pin "2") (pinfunction "2_2") (pintype "passive"))
      (node (ref "U$20") (pin "1") (pinfunction "G_1") (pintype "bidirectional"))
    )
    (net (code "61") (name "Net-(U$21-OUTPUT)") (class "Default")
      (node (ref "C4") (pin "2") (pinfunction "2_2") (pintype "passive"))
      (node (ref "U$21") (pin "P$3") (pinfunction "OUTPUT_P$3") (pintype "bidirectional"))
    )
    (net (code "62") (name "Net-(U$22-D)") (class "Default")
      (node (ref "R20") (pin "1") (pinfunction "1_1") (pintype "passive"))
      (node (ref "U$22") (pin "3") (pinfunction "D_3") (pintype "bidirectional"))
    )
    (net (code "63") (name "Net-(U$22-G)") (class "Default")
      (node (ref "R30") (pin "2") (pinfunction "2_2") (pintype "passive"))
      (node (ref "R33") (pin "2") (pinfunction "2_2") (pintype "passive"))
      (node (ref "U$22") (pin "1") (pinfunction "G_1") (pintype "bidirectional"))
    )
    (net (code "64") (name "Net-(U$23-IN-)") (class "Default")
      (node (ref "R28") (pin "1") (pinfunction "1_1") (pintype "passive"))
      (node (ref "U$23") (pin "P$4") (pinfunction "IN-_P$4") (pintype "bidirectional"))
      (node (ref "X11") (pin "3") (pinfunction "3_3") (pintype "passive"))
    )
    (net (code "65") (name "Net-(U1-PB6)") (class "Default")
      (node (ref "U1") (pin "54") (pinfunction "PD2_54") (pintype "bidirectional"))
      (node (ref "U1") (pin "58") (pinfunction "PB6_58") (pintype "bidirectional"))
    )
    (net (code "66") (name "Net-(U1-PC12)") (class "Default")
      (node (ref "R15") (pin "1") (pinfunction "1_1") (pintype "passive"))
      (node (ref "U1") (pin "53") (pinfunction "PC12_53") (pintype "bidirectional"))
    )
    (net (code "67") (name "Net-(U1-PH0{slash}OSC_IN)") (class "Default")
      (node (ref "C4") (pin "1") (pinfunction "1_1") (pintype "passive"))
      (node (ref "U1") (pin "5") (pinfunction "PH0/OSC_IN_5") (pintype "bidirectional"))
    )
    (net (code "68") (name "Net-(U1-VCAP_1)") (class "Default")
      (node (ref "C9") (pin "2") (pinfunction "2_2") (pintype "passive"))
      (node (ref "U1") (pin "31") (pinfunction "VCAP_1_31") (pintype "power_in"))
    )
    (net (code "69") (name "Net-(U1-VCAP_2)") (class "Default")
      (node (ref "C13") (pin "2") (pinfunction "2_2") (pintype "passive"))
      (node (ref "U1") (pin "47") (pinfunction "VCAP_2_47") (pintype "power_in"))
    )
    (net (code "70") (name "unconnected-(LIS3MDL-GY-CRYM-PadP$9)") (class "Default")
      (node (ref "LIS3MDL-GY") (pin "P$9") (pinfunction "CRYM_P$9") (pintype "bidirectional"))
    )
    (net (code "71") (name "unconnected-(LIS3MDL-GY-CSA-PadP$2)") (class "Default")
      (node (ref "LIS3MDL-GY") (pin "P$2") (pinfunction "CSA_P$2") (pintype "bidirectional"))
    )
    (net (code "72") (name "unconnected-(LIS3MDL-GY-CSM-PadP$1)") (class "Default")
      (node (ref "LIS3MDL-GY") (pin "P$1") (pinfunction "CSM_P$1") (pintype "bidirectional"))
    )
    (net (code "73") (name "unconnected-(LIS3MDL-GY-INTA-PadP$10)") (class "Default")
      (node (ref "LIS3MDL-GY") (pin "P$10") (pinfunction "INTA_P$10") (pintype "bidirectional"))
    )
    (net (code "74") (name "unconnected-(LIS3MDL-GY-INTM-PadP$8)") (class "Default")
      (node (ref "LIS3MDL-GY") (pin "P$8") (pinfunction "INTM_P$8") (pintype "bidirectional"))
    )
    (net (code "75") (name "unconnected-(LIS3MDL-GY-VIN-PadP$7)") (class "Default")
      (node (ref "LIS3MDL-GY") (pin "P$7") (pinfunction "VIN_P$7") (pintype "bidirectional"))
    )
    (net (code "76") (name "unconnected-(LSM6DS3-GY-CAO-PadP$1)") (class "Default")
      (node (ref "LSM6DS3-GY") (pin "P$1") (pinfunction "CAO_P$1") (pintype "bidirectional"))
    )
    (net (code "77") (name "unconnected-(LSM6DS3-GY-CS-PadP$2)") (class "Default")
      (node (ref "LSM6DS3-GY") (pin "P$2") (pinfunction "CS_P$2") (pintype "bidirectional"))
    )
    (net (code "78") (name "unconnected-(LSM6DS3-GY-DCS-PadP$12)") (class "Default")
      (node (ref "LSM6DS3-GY") (pin "P$12") (pinfunction "DCS_P$12") (pintype "bidirectional"))
    )
    (net (code "79") (name "unconnected-(LSM6DS3-GY-INT1-PadP$10)") (class "Default")
      (node (ref "LSM6DS3-GY") (pin "P$10") (pinfunction "INT1_P$10") (pintype "bidirectional"))
    )
    (net (code "80") (name "unconnected-(LSM6DS3-GY-INT2-PadP$11)") (class "Default")
      (node (ref "LSM6DS3-GY") (pin "P$11") (pinfunction "INT2_P$11") (pintype "bidirectional"))
    )
    (net (code "81") (name "unconnected-(LSM6DS3-GY-VIN-PadP$7)") (class "Default")
      (node (ref "LSM6DS3-GY") (pin "P$7") (pinfunction "VIN_P$7") (pintype "bidirectional"))
    )
    (net (code "82") (name "unconnected-(S1-S-Pad3)") (class "Default")
      (node (ref "S1") (pin "3") (pinfunction "S_3") (pintype "passive"))
    )
    (net (code "83") (name "unconnected-(U$12-12-PadP$12)") (class "Default")
      (node (ref "U$12") (pin "P$12") (pinfunction "12_P$12") (pintype "passive"))
    )
    (net (code "84") (name "unconnected-(U$12-13-PadP$13)") (class "Default")
      (node (ref "U$12") (pin "P$13") (pinfunction "13_P$13") (pintype "passive"))
    )
    (net (code "85") (name "unconnected-(U$12-14-PadP$14)") (class "Default")
      (node (ref "U$12") (pin "P$14") (pinfunction "14_P$14") (pintype "passive"))
    )
    (net (code "86") (name "unconnected-(U$12-15-PadP$15)") (class "Default")
      (node (ref "U$12") (pin "P$15") (pinfunction "15_P$15") (pintype "passive"))
    )
    (net (code "87") (name "unconnected-(U$18-STANDBY-PadP$1)") (class "Default")
      (node (ref "U$18") (pin "P$1") (pinfunction "STANDBY_P$1") (pintype "bidirectional"))
    )
    (net (code "88") (name "unconnected-(U$21-STANDBY-PadP$1)") (class "Default")
      (node (ref "U$21") (pin "P$1") (pinfunction "STANDBY_P$1") (pintype "bidirectional"))
    )
    (net (code "89") (name "unconnected-(U1-PA8-Pad41)") (class "Default")
      (node (ref "U1") (pin "41") (pinfunction "PA8_41") (pintype "bidirectional"))
    )
    (net (code "90") (name "unconnected-(U1-PA9-Pad42)") (class "Default")
      (node (ref "U1") (pin "42") (pinfunction "PA9_42") (pintype "bidirectional"))
    )
    (net (code "91") (name "unconnected-(U1-PA10-Pad43)") (class "Default")
      (node (ref "U1") (pin "43") (pinfunction "PA10_43") (pintype "bidirectional"))
    )
    (net (code "92") (name "unconnected-(U1-PA15-Pad50)") (class "Default")
      (node (ref "U1") (pin "50") (pinfunction "PA15_50") (pintype "bidirectional"))
    )
    (net (code "93") (name "unconnected-(U1-PB3-Pad55)") (class "Default")
      (node (ref "U1") (pin "55") (pinfunction "PB3_55") (pintype "bidirectional"))
    )
    (net (code "94") (name "unconnected-(U1-PB4-Pad56)") (class "Default")
      (node (ref "U1") (pin "56") (pinfunction "PB4_56") (pintype "bidirectional"))
    )
    (net (code "95") (name "unconnected-(U1-PB5-Pad57)") (class "Default")
      (node (ref "U1") (pin "57") (pinfunction "PB5_57") (pintype "bidirectional"))
    )
    (net (code "96") (name "unconnected-(U1-PB12-Pad33)") (class "Default")
      (node (ref "U1") (pin "33") (pinfunction "PB12_33") (pintype "bidirectional"))
    )
    (net (code "97") (name "unconnected-(U1-PB13-Pad34)") (class "Default")
      (node (ref "U1") (pin "34") (pinfunction "PB13_34") (pintype "bidirectional"))
    )
    (net (code "98") (name "unconnected-(U1-PB14-Pad35)") (class "Default")
      (node (ref "U1") (pin "35") (pinfunction "PB14_35") (pintype "bidirectional"))
    )
    (net (code "99") (name "unconnected-(U1-PB15-Pad36)") (class "Default")
      (node (ref "U1") (pin "36") (pinfunction "PB15_36") (pintype "bidirectional"))
    )
    (net (code "100") (name "unconnected-(U1-PC3{slash}SPI2_MOSI-Pad11)") (class "Default")
      (node (ref "U1") (pin "11") (pinfunction "PC3/SPI2_MOSI_11") (pintype "bidirectional"))
    )
    (net (code "101") (name "unconnected-(U1-PC6-Pad37)") (class "Default")
      (node (ref "U1") (pin "37") (pinfunction "PC6_37") (pintype "bidirectional"))
    )
    (net (code "102") (name "unconnected-(U1-PC7-Pad38)") (class "Default")
      (node (ref "U1") (pin "38") (pinfunction "PC7_38") (pintype "bidirectional"))
    )
    (net (code "103") (name "unconnected-(U1-PC8-Pad39)") (class "Default")
      (node (ref "U1") (pin "39") (pinfunction "PC8_39") (pintype "bidirectional"))
    )
    (net (code "104") (name "unconnected-(U1-PC9-Pad40)") (class "Default")
      (node (ref "U1") (pin "40") (pinfunction "PC9_40") (pintype "bidirectional"))
    )
    (net (code "105") (name "unconnected-(U1-PC13{slash}RTC_OUT-Pad2)") (class "Default")
      (node (ref "U1") (pin "2") (pinfunction "PC13/RTC_OUT_2") (pintype "bidirectional"))
    )
    (net (code "106") (name "unconnected-(U1-PC15{slash}OSC32_OUT-Pad4)") (class "Default")
      (node (ref "U1") (pin "4") (pinfunction "PC15/OSC32_OUT_4") (pintype "bidirectional"))
    )
    (net (code "107") (name "unconnected-(U1-PH1{slash}OSC_OUT-Pad6)") (class "Default")
      (node (ref "U1") (pin "6") (pinfunction "PH1/OSC_OUT_6") (pintype "bidirectional"))
    )
  )
)
